# uno_shield_0_1.net
KiCad netlist of a schematic drawn in EAGLE
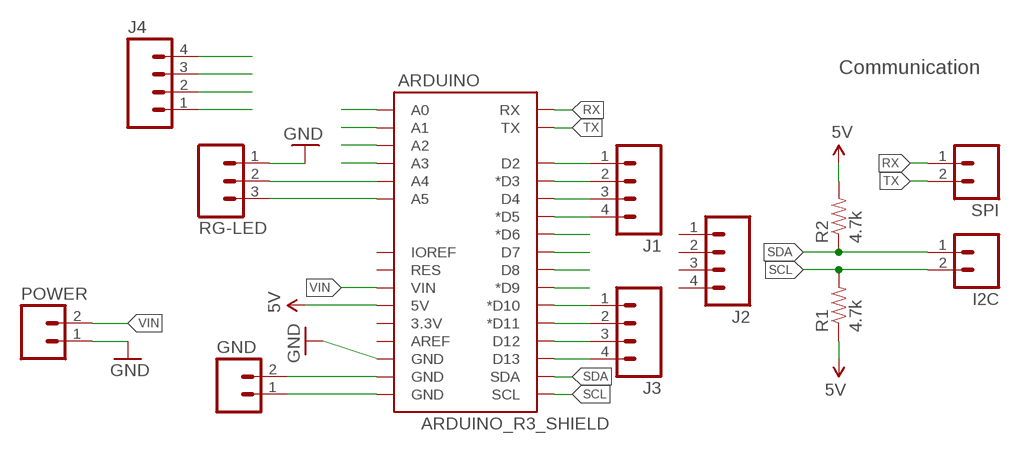
[diagram p0: schematic, sheet 1]

(export (version "E")
  (design (tool "Eeschema 10.0.6"))
  (components
    (comp (ref "ARDUINO")
      (value "ARDUINO_R3_SHIELD")
      (footprint "eagle-import:UNO_R3_SHIELD")
      (libsource (lib "eagle-import") (part "ARDUINO_R3_SHIELD"))
    )
    (comp (ref "GND")
      (value "M02LOCK_LONGPADS")
      (footprint "eagle-import:1X02_LOCK_LONGPADS")
      (libsource (lib "eagle-import") (part "M02LOCK_LONGPADS"))
    )
    (comp (ref "I2C")
      (value "M02LOCK_LONGPADS")
      (footprint "eagle-import:1X02_LOCK_LONGPADS")
      (libsource (lib "eagle-import") (part "M02LOCK_LONGPADS"))
    )
    (comp (ref "J1")
      (value "M041X04_NO_SILK")
      (footprint "eagle-import:1X04_NO_SILK")
      (libsource (lib "eagle-import") (part "M041X04_NO_SILK"))
    )
    (comp (ref "J2")
      (value "M041X04_NO_SILK")
      (footprint "eagle-import:1X04_NO_SILK")
      (libsource (lib "eagle-import") (part "M041X04_NO_SILK"))
    )
    (comp (ref "J3")
      (value "M041X04_NO_SILK")
      (footprint "eagle-import:1X04_NO_SILK")
      (libsource (lib "eagle-import") (part "M041X04_NO_SILK"))
    )
    (comp (ref "J4")
      (value "M041X04_NO_SILK")
      (footprint "eagle-import:1X04_NO_SILK")
      (libsource (lib "eagle-import") (part "M041X04_NO_SILK"))
    )
    (comp (ref "POWER")
      (value "M02LOCK_LONGPADS")
      (footprint "eagle-import:1X02_LOCK_LONGPADS")
      (libsource (lib "eagle-import") (part "M02LOCK_LONGPADS"))
    )
    (comp (ref "R1")
      (value "4.7k")
      (footprint "eagle-import:AXIAL-0.3-KIT")
      (libsource (lib "eagle-import") (part "RESISTORKIT"))
    )
    (comp (ref "R2")
      (value "4.7k")
      (footprint "eagle-import:AXIAL-0.3-KIT")
      (libsource (lib "eagle-import") (part "RESISTORKIT"))
    )
    (comp (ref "RG-LED")
      (value "M03LONGPADS")
      (footprint "eagle-import:1X03_LONGPADS")
      (libsource (lib "eagle-import") (part "M03LONGPADS"))
    )
    (comp (ref "SPI")
      (value "M02LOCK_LONGPADS")
      (footprint "eagle-import:1X02_LOCK_LONGPADS")
      (libsource (lib "eagle-import") (part "M02LOCK_LONGPADS"))
    )
  )
  (nets
    (net (code "1") (name "5V") (class "Default")
      (node (ref "ARDUINO") (pin "5V") (pinfunction "5V_5V") (pintype "bidirectional"))
      (node (ref "R1") (pin "P$1") (pinfunction "1_P$1") (pintype "passive"))
      (node (ref "R2") (pin "P$2") (pinfunction "2_P$2") (pintype "passive"))
    )
    (net (code "2") (name "GND") (class "Default")
      (node (ref "ARDUINO") (pin "GND@2") (pinfunction "GND_GND@2") (pintype "bidirectional"))
      (node (ref "POWER") (pin "1") (pinfunction "1_1") (pintype "passive"))
      (node (ref "RG-LED") (pin "1") (pinfunction "1_1") (pintype "passive"))
    )
    (net (code "3") (name "Net-(ARDUINO-*D3)") (class "Default")
      (node (ref "ARDUINO") (pin "D3") (pinfunction "*D3_D3") (pintype "bidirectional"))
      (node (ref "J1") (pin "2") (pinfunction "2_2") (pintype "passive"))
    )
    (net (code "4") (name "Net-(ARDUINO-*D5)") (class "Default")
      (node (ref "ARDUINO") (pin "D5") (pinfunction "*D5_D5") (pintype "bidirectional"))
      (node (ref "J1") (pin "4") (pinfunction "4_4") (pintype "passive"))
    )
    (net (code "5") (name "Net-(ARDUINO-*D10)") (class "Default")
      (node (ref "ARDUINO") (pin "D10") (pinfunction "*D10_D10") (pintype "bidirectional"))
      (node (ref "J3") (pin "1") (pinfunction "1_1") (pintype "passive"))
    )
    (net (code "6") (name "Net-(ARDUINO-*D11)") (class "Default")
      (node (ref "ARDUINO") (pin "D11") (pinfunction "*D11_D11") (pintype "bidirectional"))
      (node (ref "J3") (pin "2") (pinfunction "2_2") (pintype "passive"))
    )
    (net (code "7") (name "Net-(ARDUINO-GND-PadGND@0)") (class "Default")
      (node (ref "ARDUINO") (pin "GND@0") (pinfunction "GND_GND@0") (pintype "bidirectional"))
      (node (ref "GND") (pin "1") (pinfunction "1_1") (pintype "passive"))
    )
    (net (code "8") (name "Net-(ARDUINO-GND-PadGND@1)") (class "Default")
      (node (ref "ARDUINO") (pin "GND@1") (pinfunction "GND_GND@1") (pintype "bidirectional"))
      (node (ref "GND") (pin "2") (pinfunction "2_2") (pintype "passive"))
    )
    (net (code "9") (name "Net-(ARDUINO-PadA4)") (class "Default")
      (node (ref "ARDUINO") (pin "A4") (pinfunction "A4_A4") (pintype "bidirectional"))
      (node (ref "RG-LED") (pin "2") (pinfunction "2_2") (pintype "passive"))
    )
    (net (code "10") (name "Net-(ARDUINO-PadA5)") (class "Default")
      (node (ref "ARDUINO") (pin "A5") (pinfunction "A5_A5") (pintype "bidirectional"))
      (node (ref "RG-LED") (pin "3") (pinfunction "3_3") (pintype "passive"))
    )
    (net (code "11") (name "Net-(ARDUINO-PadD2)") (class "Default")
      (node (ref "ARDUINO") (pin "D2") (pinfunction "D2_D2") (pintype "bidirectional"))
      (node (ref "J1") (pin "1") (pinfunction "1_1") (pintype "passive"))
    )
    (net (code "12") (name "Net-(ARDUINO-PadD4)") (class "Default")
      (node (ref "ARDUINO") (pin "D4") (pinfunction "D4_D4") (pintype "bidirectional"))
      (node (ref "J1") (pin "3") (pinfunction "3_3") (pintype "passive"))
    )
    (net (code "13") (name "Net-(ARDUINO-PadD12)") (class "Default")
      (node (ref "ARDUINO") (pin "D12") (pinfunction "D12_D12") (pintype "bidirectional"))
      (node (ref "J3") (pin "3") (pinfunction "3_3") (pintype "passive"))
    )
    (net (code "14") (name "Net-(ARDUINO-PadD13)") (class "Default")
      (node (ref "ARDUINO") (pin "D13") (pinfunction "D13_D13") (pintype "bidirectional"))
      (node (ref "J3") (pin "4") (pinfunction "4_4") (pintype "passive"))
    )
    (net (code "15") (name "RX") (class "Default")
      (node (ref "ARDUINO") (pin "RX") (pinfunction "RX_RX") (pintype "bidirectional"))
      (node (ref "SPI") (pin "1") (pinfunction "1_1") (pintype "passive"))
    )
    (net (code "16") (name "SCL") (class "Default")
      (node (ref "ARDUINO") (pin "SCL") (pinfunction "SCL_SCL") (pintype "bidirectional"))
      (node (ref "I2C") (pin "2") (pinfunction "2_2") (pintype "passive"))
      (node (ref "R1") (pin "P$2") (pinfunction "2_P$2") (pintype "passive"))
    )
    (net (code "17") (name "SDA") (class "Default")
      (node (ref "ARDUINO") (pin "SDA") (pinfunction "SDA_SDA") (pintype "bidirectional"))
      (node (ref "I2C") (pin "1") (pinfunction "1_1") (pintype "passive"))
      (node (ref "R2") (pin "P$1") (pinfunction "1_P$1") (pintype "passive"))
    )
    (net (code "18") (name "TX") (class "Default")
      (node (ref "ARDUINO") (pin "TX") (pinfunction "TX_TX") (pintype "bidirectional"))
      (node (ref "SPI") (pin "2") (pinfunction "2_2") (pintype "passive"))
    )
    (net (code "19") (name "VIN") (class "Default")
      (node (ref "ARDUINO") (pin "VIN") (pinfunction "VIN_VIN") (pintype "bidirectional"))
      (node (ref "POWER") (pin "2") (pinfunction "2_2") (pintype "passive"))
    )
    (net (code "20") (name "unconnected-(ARDUINO-*D6-PadD6)") (class "Default")
      (node (ref "ARDUINO") (pin "D6") (pinfunction "*D6_D6") (pintype "bidirectional"))
    )
    (net (code "21") (name "unconnected-(ARDUINO-*D9-PadD9)") (class "Default")
      (node (ref "ARDUINO") (pin "D9") (pinfunction "*D9_D9") (pintype "bidirectional"))
    )
    (net (code "22") (name "unconnected-(ARDUINO-Pad3.3V)") (class "Default")
      (node (ref "ARDUINO") (pin "3.3V") (pinfunction "3.3V_3.3V") (pintype "bidirectional"))
    )
    (net (code "23") (name "unconnected-(ARDUINO-PadA0)") (class "Default")
      (node (ref "ARDUINO") (pin "A0") (pinfunction "A0_A0") (pintype "bidirectional"))
    )
    (net (code "24") (name "unconnected-(ARDUINO-PadA1)") (class "Default")
      (node (ref "ARDUINO") (pin "A1") (pinfunction "A1_A1") (pintype "bidirectional"))
    )
    (net (code "25") (name "unconnected-(ARDUINO-PadA2)") (class "Default")
      (node (ref "ARDUINO") (pin "A2") (pinfunction "A2_A2") (pintype "bidirectional"))
    )
    (net (code "26") (name "unconnected-(ARDUINO-PadA3)") (class "Default")
      (node (ref "ARDUINO") (pin "A3") (pinfunction "A3_A3") (pintype "bidirectional"))
    )
    (net (code "27") (name "unconnected-(ARDUINO-PadAREF)") (class "Default")
      (node (ref "ARDUINO") (pin "AREF") (pinfunction "AREF_AREF") (pintype "bidirectional"))
    )
    (net (code "28") (name "unconnected-(ARDUINO-PadD7)") (class "Default")
      (node (ref "ARDUINO") (pin "D7") (pinfunction "D7_D7") (pintype "bidirectional"))
    )
    (net (code "29") (name "unconnected-(ARDUINO-PadD8)") (class "Default")
      (node (ref "ARDUINO") (pin "D8") (pinfunction "D8_D8") (pintype "bidirectional"))
    )
    (net (code "30") (name "unconnected-(ARDUINO-PadIOREF)") (class "Default")
      (node (ref "ARDUINO") (pin "IOREF") (pinfunction "IOREF_IOREF") (pintype "bidirectional"))
    )
    (net (code "31") (name "unconnected-(ARDUINO-PadRES)") (class "Default")
      (node (ref "ARDUINO") (pin "RES") (pinfunction "RES_RES") (pintype "bidirectional"))
    )
    (net (code "32") (name "unconnected-(J2-Pad1)") (class "Default")
      (node (ref "J2") (pin "1") (pinfunction "1_1") (pintype "passive"))
    )
    (net (code "33") (name "unconnected-(J2-Pad2)") (class "Default")
      (node (ref "J2") (pin "2") (pinfunction "2_2") (pintype "passive"))
    )
    (net (code "34") (name "unconnected-(J2-Pad3)") (class "Default")
      (node (ref "J2") (pin "3") (pinfunction "3_3") (pintype "passive"))
    )
    (net (code "35") (name "unconnected-(J2-Pad4)") (class "Default")
      (node (ref "J2") (pin "4") (pinfunction "4_4") (pintype "passive"))
    )
    (net (code "36") (name "unconnected-(J4-Pad1)") (class "Default")
      (node (ref "J4") (pin "1") (pinfunction "1_1") (pintype "passive"))
    )
    (net (code "37") (name "unconnected-(J4-Pad2)") (class "Default")
      (node (ref "J4") (pin "2") (pinfunction "2_2") (pintype "passive"))
    )
    (net (code "38") (name "unconnected-(J4-Pad3)") (class "Default")
      (node (ref "J4") (pin "3") (pinfunction "3_3") (pintype "passive"))
    )
    (net (code "39") (name "unconnected-(J4-Pad4)") (class "Default")
      (node (ref "J4") (pin "4") (pinfunction "4_4") (pintype "passive"))
    )
  )
)
